# RefOsc10MHz_2V3.net
KiCad netlist of a schematic drawn in EAGLE
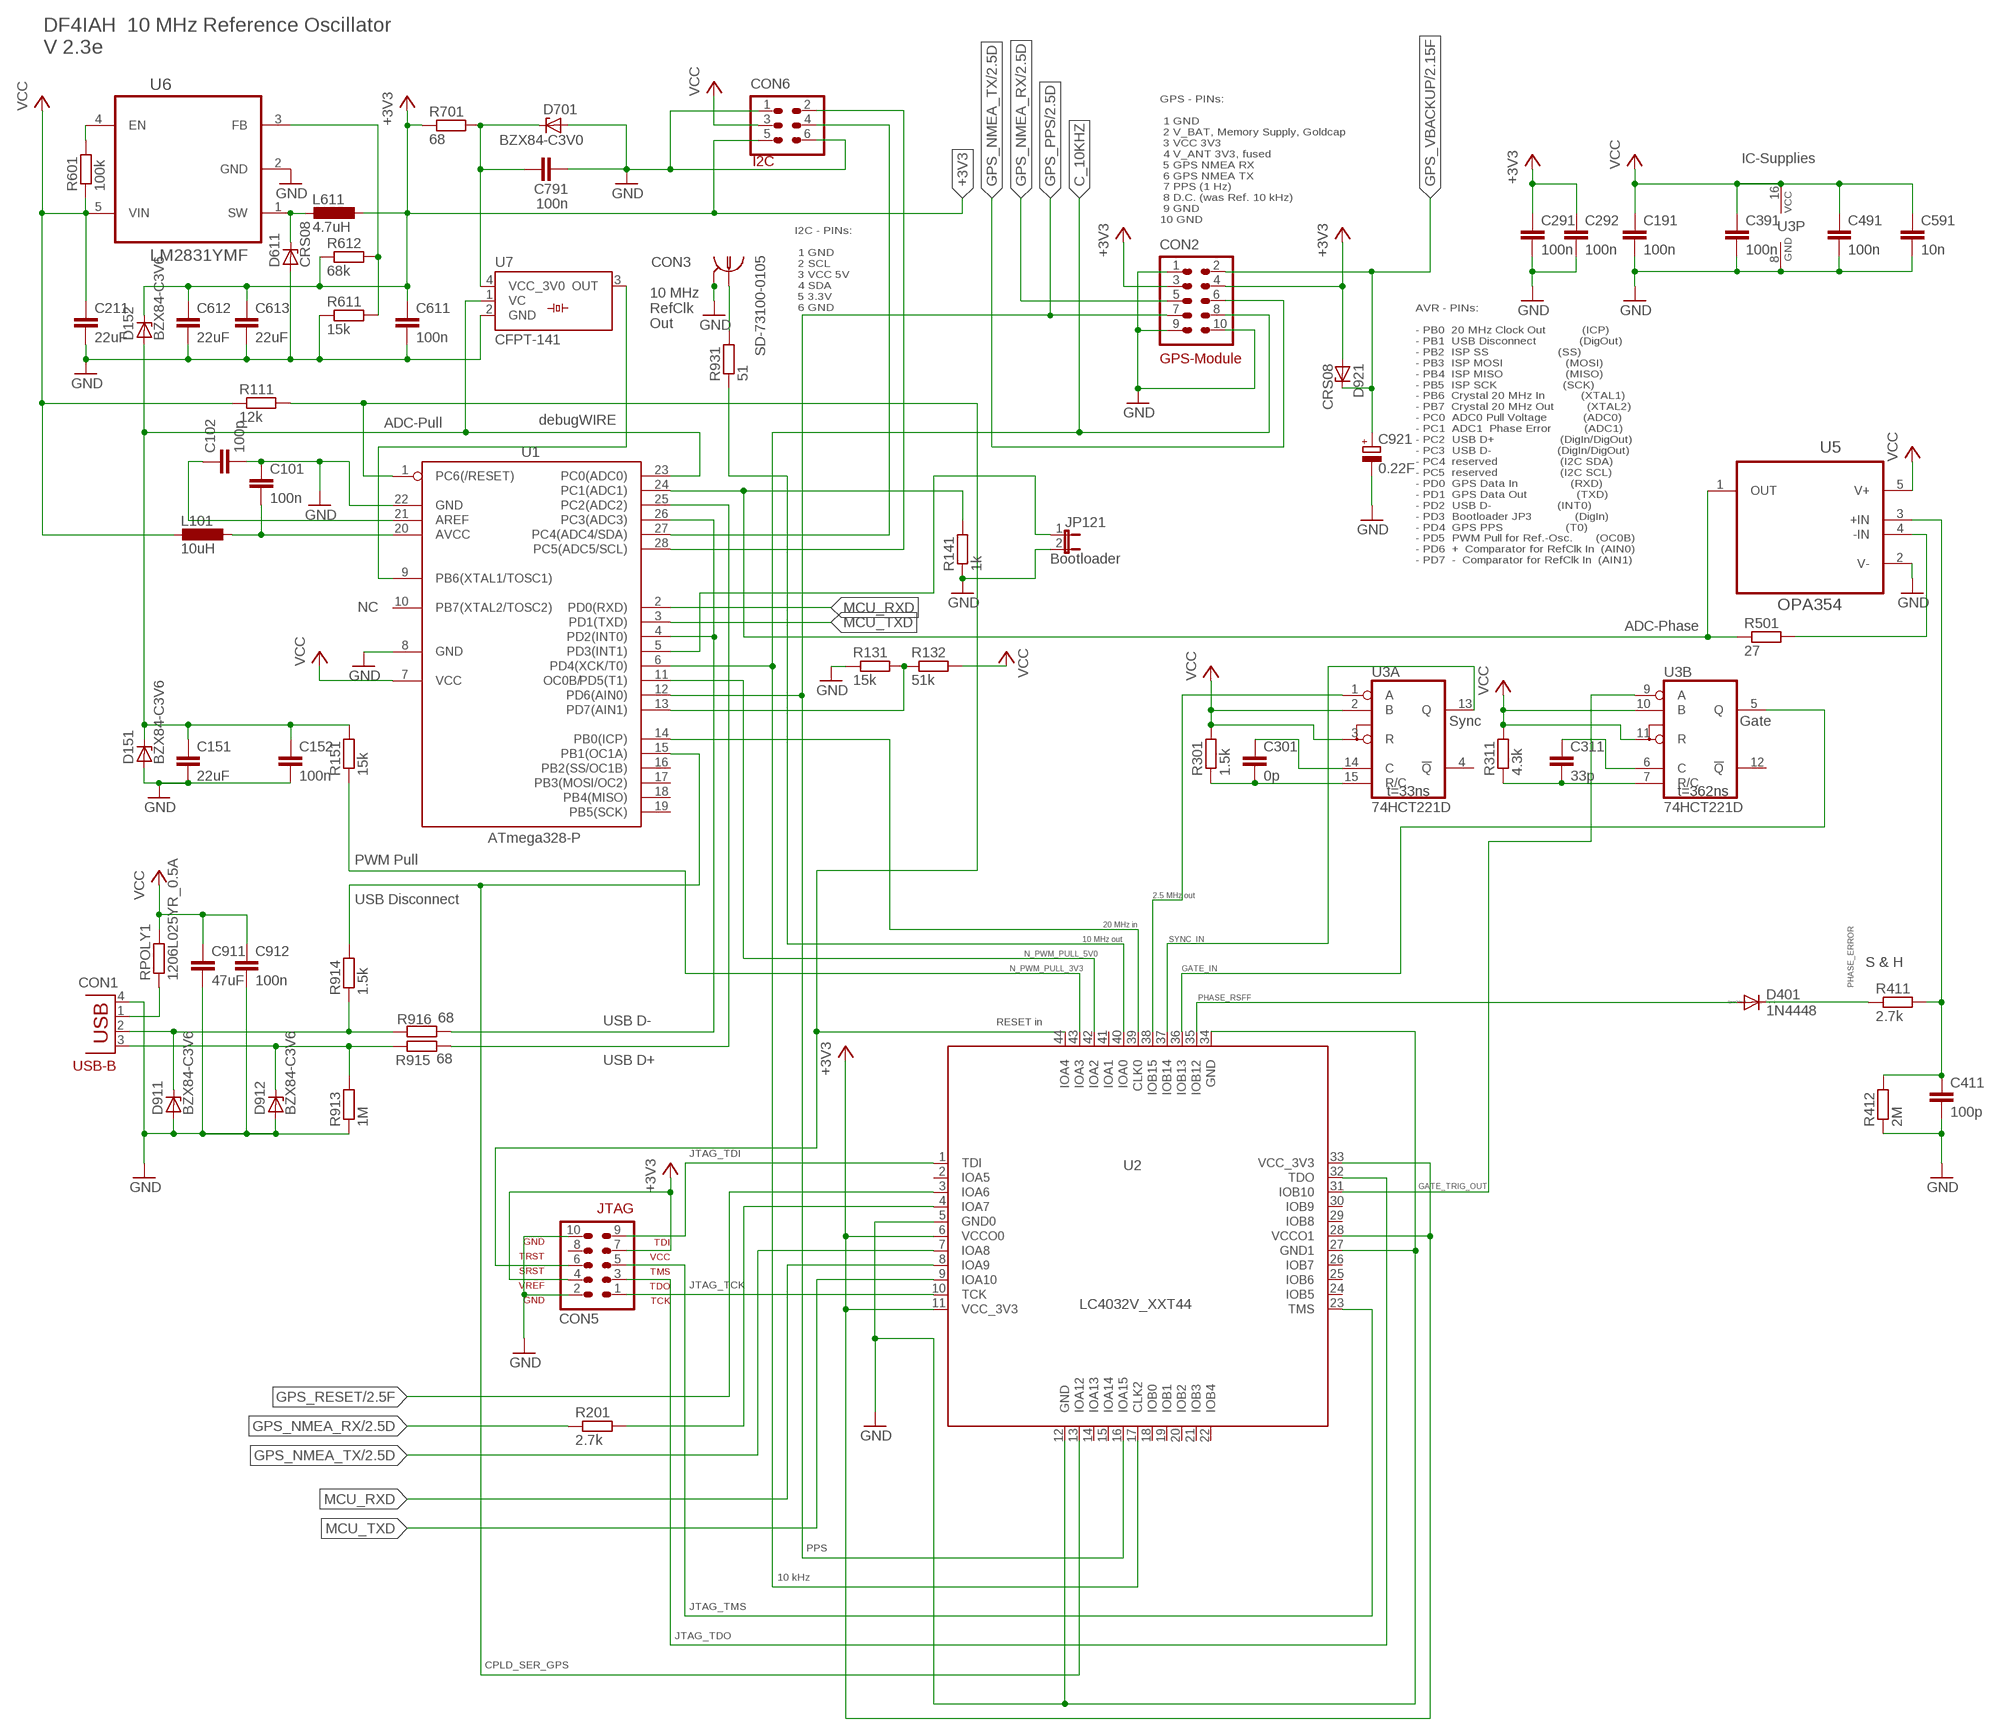
[diagram p0: schematic, sheet 1]
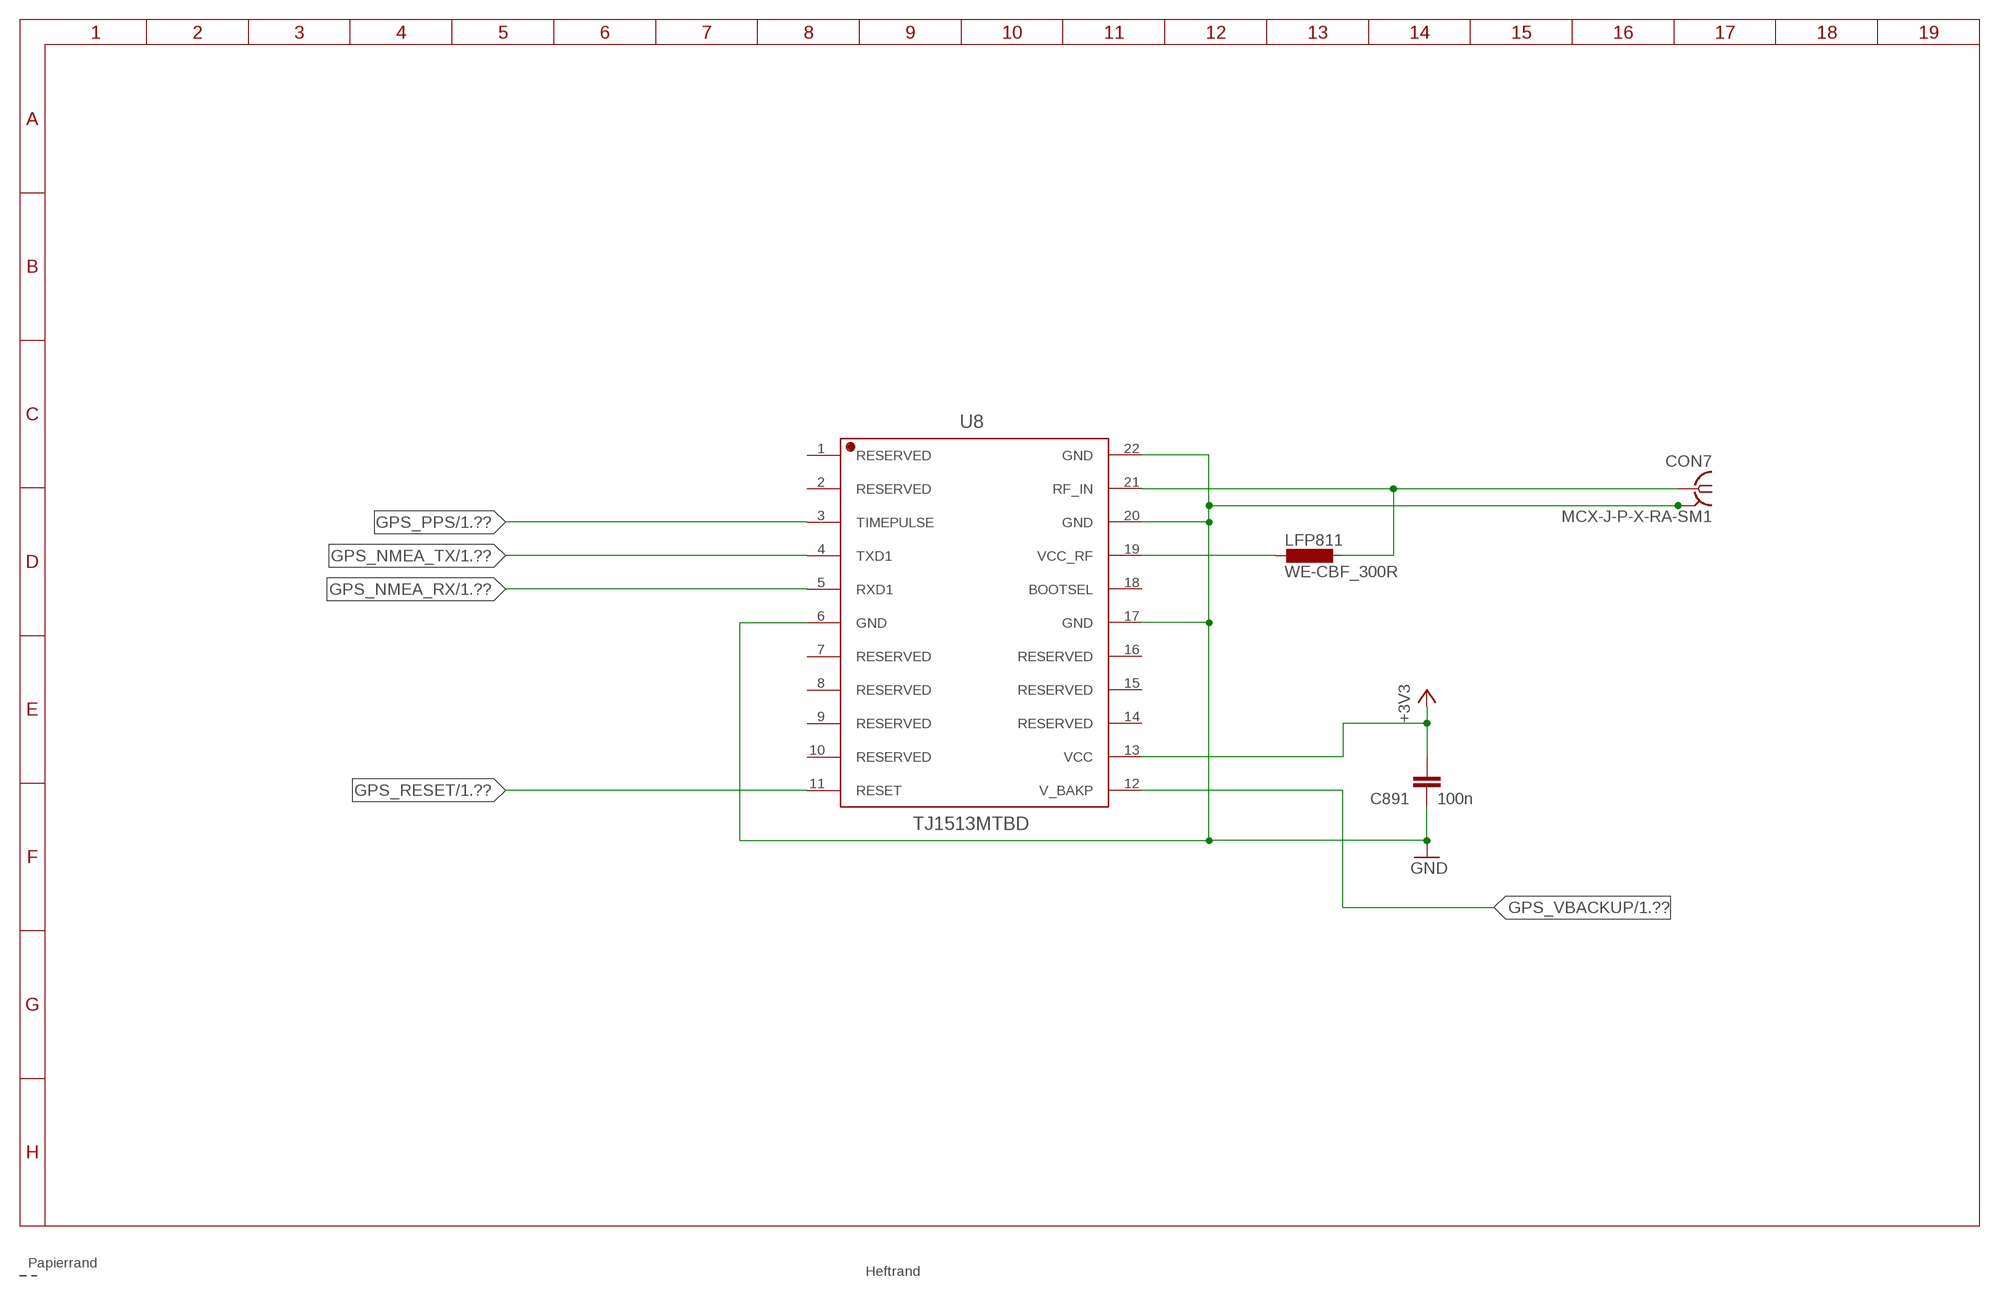
[diagram p1: schematic, sheet 2]
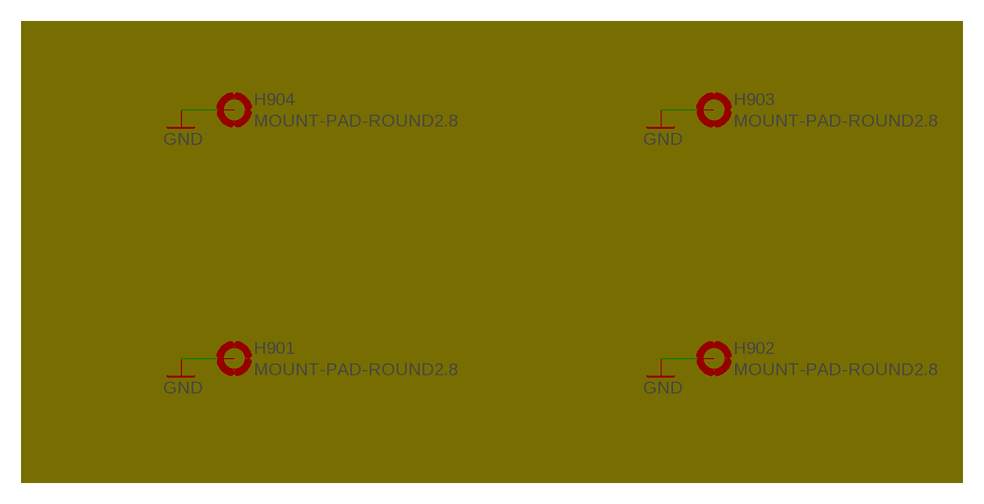
[diagram p2: schematic, sheet 3]

(export (version "E")
  (design (tool "Eeschema 10.0.6"))
  (components
    (comp (ref "C101")
      (value "100n")
      (footprint "eagle-import:C0805")
      (libsource (lib "eagle-import") (part "rcl_C-EUC0805"))
    )
    (comp (ref "C102")
      (value "100p")
      (footprint "eagle-import:C0805")
      (libsource (lib "eagle-import") (part "rcl_C-EUC0805"))
    )
    (comp (ref "C151")
      (value "22uF")
      (footprint "eagle-import:C0805")
      (libsource (lib "eagle-import") (part "rcl_C-EUC0805"))
    )
    (comp (ref "C152")
      (value "100n")
      (footprint "eagle-import:C0805")
      (libsource (lib "eagle-import") (part "rcl_C-EUC0805"))
    )
    (comp (ref "C191")
      (value "100n")
      (footprint "eagle-import:C0805")
      (libsource (lib "eagle-import") (part "rcl_C-EUC0805"))
    )
    (comp (ref "C211")
      (value "22uF")
      (footprint "eagle-import:C0805")
      (libsource (lib "eagle-import") (part "rcl_C-EUC0805"))
    )
    (comp (ref "C291")
      (value "100n")
      (footprint "eagle-import:C0805")
      (libsource (lib "eagle-import") (part "rcl_C-EUC0805"))
    )
    (comp (ref "C292")
      (value "100n")
      (footprint "eagle-import:C0805")
      (libsource (lib "eagle-import") (part "rcl_C-EUC0805"))
    )
    (comp (ref "C301")
      (value "0p")
      (footprint "eagle-import:C0805")
      (libsource (lib "eagle-import") (part "rcl_C-EUC0805"))
    )
    (comp (ref "C311")
      (value "33p")
      (footprint "eagle-import:C0805")
      (libsource (lib "eagle-import") (part "rcl_C-EUC0805"))
    )
    (comp (ref "C391")
      (value "100n")
      (footprint "eagle-import:C0805")
      (libsource (lib "eagle-import") (part "rcl_C-EUC0805"))
    )
    (comp (ref "C411")
      (value "100p")
      (footprint "eagle-import:C0805")
      (libsource (lib "eagle-import") (part "rcl_C-EUC0805"))
    )
    (comp (ref "C491")
      (value "100n")
      (footprint "eagle-import:C0805")
      (libsource (lib "eagle-import") (part "rcl_C-EUC0805"))
    )
    (comp (ref "C591")
      (value "10n")
      (footprint "eagle-import:C0805")
      (libsource (lib "eagle-import") (part "rcl_C-EUC0805"))
    )
    (comp (ref "C611")
      (value "100n")
      (footprint "eagle-import:C0805")
      (libsource (lib "eagle-import") (part "rcl_C-EUC0805"))
    )
    (comp (ref "C612")
      (value "22uF")
      (footprint "eagle-import:C0805")
      (libsource (lib "eagle-import") (part "rcl_C-EUC0805"))
    )
    (comp (ref "C613")
      (value "22uF")
      (footprint "eagle-import:C0805")
      (libsource (lib "eagle-import") (part "rcl_C-EUC0805"))
    )
    (comp (ref "C791")
      (value "100n")
      (footprint "eagle-import:C0805")
      (libsource (lib "eagle-import") (part "rcl_C-EUC0805"))
    )
    (comp (ref "C911")
      (value "47uF")
      (footprint "eagle-import:C0805")
      (libsource (lib "eagle-import") (part "rcl_C-EUC0805"))
    )
    (comp (ref "C912")
      (value "100n")
      (footprint "eagle-import:C0805")
      (libsource (lib "eagle-import") (part "rcl_C-EUC0805"))
    )
    (comp (ref "C921")
      (value "0.22F")
      (footprint "eagle-import:140CLH-1010")
      (libsource (lib "eagle-import") (part "CPOL-EU140CLH-1010"))
    )
    (comp (ref "CON1")
      (value "TYCO-AMP_USBUSB-B_SMT")
      (footprint "eagle-import:TYCO-AMP_USB-B_SMT")
      (fields (field (name "MF") "TYCO-AMP") (field (name "MPN") "1734346"))
      (libsource (lib "eagle-import") (part "TYCO-AMP_USBUSB-B_SMT"))
    )
    (comp (ref "CON2")
      (value "HEADER-2X5")
      (footprint "eagle-import:2X05")
      (libsource (lib "eagle-import") (part "HEADER-2X5"))
    )
    (comp (ref "CON3")
      (value "SD-73100-0105")
      (footprint "eagle-import:MOLEX_BNC-JACK-50R_SD-73100-0105")
      (fields (field (name "MF") "MOLEX"))
      (libsource (lib "eagle-import") (part "MOLEX_BNC-JACK-50R_SD-73100-0105"))
    )
    (comp (ref "CON5")
      (value "AVR-JTAG-10")
      (footprint "eagle-import:AVR-JTAG-10")
      (libsource (lib "eagle-import") (part "AVR-JTAG-10"))
    )
    (comp (ref "CON6")
      (value "HEADER-2X3")
      (footprint "eagle-import:2X03")
      (libsource (lib "eagle-import") (part "HEADER-2X3"))
    )
    (comp (ref "D151")
      (value "BZX84-C3V6")
      (footprint "eagle-import:TO236")
      (libsource (lib "eagle-import") (part "BZX84CSMD"))
    )
    (comp (ref "D152")
      (value "BZX84-C3V6")
      (footprint "eagle-import:TO236")
      (libsource (lib "eagle-import") (part "BZX84CSMD"))
    )
    (comp (ref "D401")
      (value "1N4448")
      (footprint "eagle-import:DO35-7")
      (libsource (lib "eagle-import") (part "1N4148DO35-7"))
    )
    (comp (ref "D611")
      (value "CRS08")
      (footprint "eagle-import:SOD80C")
      (libsource (lib "eagle-import") (part "ZENER-DIODESOD80C"))
    )
    (comp (ref "D701")
      (value "BZX84-C3V0")
      (footprint "eagle-import:TO236")
      (libsource (lib "eagle-import") (part "BZX84CSMD"))
    )
    (comp (ref "D911")
      (value "BZX84-C3V6")
      (footprint "eagle-import:TO236")
      (libsource (lib "eagle-import") (part "BZX84CSMD"))
    )
    (comp (ref "D912")
      (value "BZX84-C3V6")
      (footprint "eagle-import:TO236")
      (libsource (lib "eagle-import") (part "BZX84CSMD"))
    )
    (comp (ref "D921")
      (value "CRS08")
      (footprint "eagle-import:SOD80C")
      (libsource (lib "eagle-import") (part "ZENER-DIODESOD80C"))
    )
    (comp (ref "JP121")
      (value "JP1E")
      (footprint "eagle-import:JP1")
      (libsource (lib "eagle-import") (part "JP1E"))
    )
    (comp (ref "L101")
      (value "10uH")
      (footprint "eagle-import:L1812")
      (libsource (lib "eagle-import") (part "rcl_L-EUL1812"))
    )
    (comp (ref "L611")
      (value "4.7uH")
      (footprint "eagle-import:L5650M")
      (libsource (lib "eagle-import") (part "rcl_L-EUL5650M"))
    )
    (comp (ref "R111")
      (value "12k")
      (footprint "eagle-import:R0805")
      (libsource (lib "eagle-import") (part "R-EU_R0805"))
    )
    (comp (ref "R131")
      (value "15k")
      (footprint "eagle-import:R0805")
      (libsource (lib "eagle-import") (part "R-EU_R0805"))
    )
    (comp (ref "R132")
      (value "51k")
      (footprint "eagle-import:R0805")
      (libsource (lib "eagle-import") (part "R-EU_R0805"))
    )
    (comp (ref "R141")
      (value "1k")
      (footprint "eagle-import:R0805")
      (libsource (lib "eagle-import") (part "R-EU_R0805"))
    )
    (comp (ref "R151")
      (value "15k")
      (footprint "eagle-import:R0805")
      (libsource (lib "eagle-import") (part "R-EU_R0805"))
    )
    (comp (ref "R201")
      (value "2.7k")
      (footprint "eagle-import:R0805")
      (libsource (lib "eagle-import") (part "R-EU_R0805"))
    )
    (comp (ref "R301")
      (value "1.5k")
      (footprint "eagle-import:R0805")
      (libsource (lib "eagle-import") (part "R-EU_R0805"))
    )
    (comp (ref "R311")
      (value "4.3k")
      (footprint "eagle-import:R0805")
      (libsource (lib "eagle-import") (part "R-EU_R0805"))
    )
    (comp (ref "R411")
      (value "2.7k")
      (footprint "eagle-import:R0805")
      (libsource (lib "eagle-import") (part "R-EU_R0805"))
    )
    (comp (ref "R412")
      (value "2M")
      (footprint "eagle-import:R0805")
      (libsource (lib "eagle-import") (part "R-EU_R0805"))
    )
    (comp (ref "R501")
      (value "27")
      (footprint "eagle-import:R0805")
      (libsource (lib "eagle-import") (part "R-EU_R0805"))
    )
    (comp (ref "R601")
      (value "100k")
      (footprint "eagle-import:R0805")
      (libsource (lib "eagle-import") (part "R-EU_R0805"))
    )
    (comp (ref "R611")
      (value "15k")
      (footprint "eagle-import:R0805")
      (libsource (lib "eagle-import") (part "R-EU_R0805"))
    )
    (comp (ref "R612")
      (value "68k")
      (footprint "eagle-import:R0805")
      (libsource (lib "eagle-import") (part "R-EU_R0805"))
    )
    (comp (ref "R701")
      (value "68")
      (footprint "eagle-import:R0805")
      (libsource (lib "eagle-import") (part "R-EU_R0805"))
    )
    (comp (ref "R913")
      (value "1M")
      (footprint "eagle-import:R0805")
      (libsource (lib "eagle-import") (part "R-EU_R0805"))
    )
    (comp (ref "R914")
      (value "1.5k")
      (footprint "eagle-import:R0805")
      (libsource (lib "eagle-import") (part "R-EU_R0805"))
    )
    (comp (ref "R915")
      (value "68")
      (footprint "eagle-import:R0805")
      (libsource (lib "eagle-import") (part "R-EU_R0805"))
    )
    (comp (ref "R916")
      (value "68")
      (footprint "eagle-import:R0805")
      (libsource (lib "eagle-import") (part "R-EU_R0805"))
    )
    (comp (ref "R931")
      (value "51")
      (footprint "eagle-import:R0805")
      (libsource (lib "eagle-import") (part "R-EU_R0805"))
    )
    (comp (ref "RPOLY1")
      (value "1206L025YR_0.5A")
      (footprint "eagle-import:M1206")
      (libsource (lib "eagle-import") (part "R-EU_M1206"))
    )
    (comp (ref "U1")
      (value "ATmega328-P")
      (footprint "eagle-import:DIL28-3")
      (libsource (lib "eagle-import") (part "MEGA8-P"))
    )
    (comp (ref "U2")
      (value "LC4032V_XXT44")
      (footprint "eagle-import:TQFP44")
      (libsource (lib "eagle-import") (part "LC4032V_XXT44"))
    )
    (comp (ref "U3")
      (value "74HCT221D")
      (footprint "eagle-import:SO16")
      (libsource (lib "eagle-import") (part "74221DHCT"))
    )
    (comp (ref "U5")
      (value "OPA354")
      (footprint "eagle-import:SOT-23-5")
      (fields (field (name "MPN") "OPA354AIDBVT"))
      (libsource (lib "eagle-import") (part "OPA354"))
    )
    (comp (ref "U6")
      (value "LM2831YMF")
      (footprint "eagle-import:SOT95P280X145-5N")
      (fields (field (name "MPN") "LM2831YMF/NOPB"))
      (libsource (lib "eagle-import") (part "LM2831YMF"))
    )
    (comp (ref "U7")
      (value "CFPT-141")
      (footprint "eagle-import:CFPT-141")
      (fields (field (name "MF") "IQD-FREQUENCY-PRODUCTS") (field (name "MPN") "LFTVXO022175"))
      (libsource (lib "eagle-import") (part "CFPT-141"))
    )
    (comp (ref "H901")
      (value "MOUNT-PAD-ROUND2.8")
      (footprint "eagle-import:2,8-PAD")
      (libsource (lib "eagle-import") (part "MOUNT-PAD-ROUND2.8"))
    )
    (comp (ref "H902")
      (value "MOUNT-PAD-ROUND2.8")
      (footprint "eagle-import:2,8-PAD")
      (libsource (lib "eagle-import") (part "MOUNT-PAD-ROUND2.8"))
    )
    (comp (ref "H903")
      (value "MOUNT-PAD-ROUND2.8")
      (footprint "eagle-import:2,8-PAD")
      (libsource (lib "eagle-import") (part "MOUNT-PAD-ROUND2.8"))
    )
    (comp (ref "H904")
      (value "MOUNT-PAD-ROUND2.8")
      (footprint "eagle-import:2,8-PAD")
      (libsource (lib "eagle-import") (part "MOUNT-PAD-ROUND2.8"))
    )
    (comp (ref "C891")
      (value "100n")
      (footprint "eagle-import:C0805")
      (libsource (lib "eagle-import") (part "C-EUC0805"))
    )
    (comp (ref "CON7")
      (value "MCX-J-P-X-RA-SM1")
      (footprint "eagle-import:MCX-J-P-X-RA-SM1")
      (libsource (lib "eagle-import") (part "MCX-J-P-X-RA-SM1"))
    )
    (comp (ref "LFP811")
      (value "WE-CBF_300R")
      (footprint "eagle-import:L3216C")
      (libsource (lib "eagle-import") (part "L-EUL3216C"))
    )
    (comp (ref "U8")
      (value "TJ1513MTBD")
      (footprint "eagle-import:TJ1513MTBD")
      (libsource (lib "eagle-import") (part "TJ1513MTBD"))
    )
  )
  (nets
    (net (code "1") (name "+3V3") (class "Default")
      (node (ref "C291") (pin "1") (pinfunction "1_1") (pintype "passive"))
      (node (ref "C292") (pin "1") (pinfunction "1_1") (pintype "passive"))
      (node (ref "C611") (pin "1") (pinfunction "1_1") (pintype "passive"))
      (node (ref "C612") (pin "1") (pinfunction "1_1") (pintype "passive"))
      (node (ref "C613") (pin "1") (pinfunction "1_1") (pintype "passive"))
      (node (ref "C891") (pin "1") (pinfunction "1_1") (pintype "passive"))
      (node (ref "CON2") (pin "3") (pinfunction "3_3") (pintype "passive"))
      (node (ref "CON2") (pin "4") (pinfunction "4_4") (pintype "passive"))
      (node (ref "CON5") (pin "4") (pinfunction "4_4") (pintype "passive"))
      (node (ref "CON5") (pin "7") (pinfunction "7_7") (pintype "passive"))
      (node (ref "CON6") (pin "5") (pinfunction "5_5") (pintype "passive"))
      (node (ref "D152") (pin "C") (pinfunction "C_C") (pintype "passive"))
      (node (ref "D921") (pin "A") (pinfunction "A_A") (pintype "passive"))
      (node (ref "L611") (pin "1") (pinfunction "1_1") (pintype "passive"))
      (node (ref "R612") (pin "1") (pinfunction "1_1") (pintype "passive"))
      (node (ref "R701") (pin "1") (pinfunction "1_1") (pintype "passive"))
      (node (ref "U2") (pin "11") (pinfunction "VCC_3V3_11") (pintype "power_in"))
      (node (ref "U2") (pin "28") (pinfunction "VCCO1_28") (pintype "power_in"))
      (node (ref "U2") (pin "33") (pinfunction "VCC_3V3_33") (pintype "power_in"))
      (node (ref "U2") (pin "6") (pinfunction "VCCO0_6") (pintype "power_in"))
      (node (ref "U8") (pin "13") (pinfunction "VCC_13") (pintype "power_in"))
    )
    (net (code "2") (name "C_10KHZ") (class "Default")
      (node (ref "CON2") (pin "8") (pinfunction "8_8") (pintype "passive"))
      (node (ref "U1") (pin "6") (pinfunction "PD4(XCK/T0)_6") (pintype "bidirectional"))
      (node (ref "U2") (pin "17") (pinfunction "CLK2_17") (pintype "input"))
    )
    (net (code "3") (name "GATE_IN") (class "Default")
      (node (ref "U2") (pin "36") (pinfunction "IOB13_36") (pintype "bidirectional"))
      (node (ref "U3") (pin "5") (pinfunction "Q_5") (pintype "output"))
    )
    (net (code "4") (name "GATE_TRIG_OUT") (class "Default")
      (node (ref "U2") (pin "31") (pinfunction "IOB10_31") (pintype "bidirectional"))
      (node (ref "U3") (pin "9") (pinfunction "A_9") (pintype "input"))
    )
    (net (code "5") (name "GND") (class "Default")
      (node (ref "C101") (pin "1") (pinfunction "1_1") (pintype "passive"))
      (node (ref "C102") (pin "2") (pinfunction "2_2") (pintype "passive"))
      (node (ref "C151") (pin "2") (pinfunction "2_2") (pintype "passive"))
      (node (ref "C152") (pin "2") (pinfunction "2_2") (pintype "passive"))
      (node (ref "C191") (pin "2") (pinfunction "2_2") (pintype "passive"))
      (node (ref "C211") (pin "2") (pinfunction "2_2") (pintype "passive"))
      (node (ref "C291") (pin "2") (pinfunction "2_2") (pintype "passive"))
      (node (ref "C292") (pin "2") (pinfunction "2_2") (pintype "passive"))
      (node (ref "C391") (pin "2") (pinfunction "2_2") (pintype "passive"))
      (node (ref "C411") (pin "2") (pinfunction "2_2") (pintype "passive"))
      (node (ref "C491") (pin "2") (pinfunction "2_2") (pintype "passive"))
      (node (ref "C591") (pin "2") (pinfunction "2_2") (pintype "passive"))
      (node (ref "C611") (pin "2") (pinfunction "2_2") (pintype "passive"))
      (node (ref "C612") (pin "2") (pinfunction "2_2") (pintype "passive"))
      (node (ref "C613") (pin "2") (pinfunction "2_2") (pintype "passive"))
      (node (ref "C791") (pin "2") (pinfunction "2_2") (pintype "passive"))
      (node (ref "C891") (pin "2") (pinfunction "2_2") (pintype "passive"))
      (node (ref "C911") (pin "2") (pinfunction "2_2") (pintype "passive"))
      (node (ref "C912") (pin "2") (pinfunction "2_2") (pintype "passive"))
      (node (ref "C921") (pin "-") (pinfunction "-_-") (pintype "passive"))
      (node (ref "CON1") (pin "4") (pinfunction "GND_4") (pintype "bidirectional"))
      (node (ref "CON2") (pin "1") (pinfunction "1_1") (pintype "passive"))
      (node (ref "CON2") (pin "10") (pinfunction "10_10") (pintype "passive"))
      (node (ref "CON2") (pin "9") (pinfunction "9_9") (pintype "passive"))
      (node (ref "CON3") (pin "2") (pinfunction "2_2") (pintype "passive"))
      (node (ref "CON3") (pin "3") (pinfunction "3_3") (pintype "passive"))
      (node (ref "CON5") (pin "10") (pinfunction "10_10") (pintype "passive"))
      (node (ref "CON5") (pin "2") (pinfunction "2_2") (pintype "passive"))
      (node (ref "CON6") (pin "1") (pinfunction "1_1") (pintype "passive"))
      (node (ref "CON6") (pin "6") (pinfunction "6_6") (pintype "passive"))
      (node (ref "CON7") (pin "2") (pinfunction "2_2") (pintype "passive"))
      (node (ref "CON7") (pin "3") (pinfunction "3_3") (pintype "passive"))
      (node (ref "CON7") (pin "4") (pinfunction "4_4") (pintype "passive"))
      (node (ref "CON7") (pin "5") (pinfunction "5_5") (pintype "passive"))
      (node (ref "D151") (pin "A") (pinfunction "A_A") (pintype "passive"))
      (node (ref "D611") (pin "A") (pinfunction "A_A") (pintype "passive"))
      (node (ref "D701") (pin "A") (pinfunction "A_A") (pintype "passive"))
      (node (ref "D911") (pin "A") (pinfunction "A_A") (pintype "passive"))
      (node (ref "D912") (pin "A") (pinfunction "A_A") (pintype "passive"))
      (node (ref "H901") (pin "B2,8") (pinfunction "MOUNT_B2,8") (pintype "passive"))
      (node (ref "H902") (pin "B2,8") (pinfunction "MOUNT_B2,8") (pintype "passive"))
      (node (ref "H903") (pin "B2,8") (pinfunction "MOUNT_B2,8") (pintype "passive"))
      (node (ref "H904") (pin "B2,8") (pinfunction "MOUNT_B2,8") (pintype "passive"))
      (node (ref "JP121") (pin "2") (pinfunction "2_2") (pintype "passive"))
      (node (ref "R131") (pin "1") (pinfunction "1_1") (pintype "passive"))
      (node (ref "R141") (pin "1") (pinfunction "1_1") (pintype "passive"))
      (node (ref "R412") (pin "1") (pinfunction "1_1") (pintype "passive"))
      (node (ref "R611") (pin "1") (pinfunction "1_1") (pintype "passive"))
      (node (ref "R913") (pin "1") (pinfunction "1_1") (pintype "passive"))
      (node (ref "U1") (pin "22") (pinfunction "GND_22") (pintype "power_in"))
      (node (ref "U1") (pin "8") (pinfunction "GND_8") (pintype "power_in"))
      (node (ref "U2") (pin "12") (pinfunction "GND_12") (pintype "power_in"))
      (node (ref "U2") (pin "27") (pinfunction "GND1_27") (pintype "power_in"))
      (node (ref "U2") (pin "34") (pinfunction "GND_34") (pintype "power_in"))
      (node (ref "U2") (pin "5") (pinfunction "GND0_5") (pintype "power_in"))
      (node (ref "U3") (pin "8") (pinfunction "GND_8") (pintype "power_in"))
      (node (ref "U5") (pin "2") (pinfunction "V-_2") (pintype "power_in"))
      (node (ref "U6") (pin "2") (pinfunction "GND_2") (pintype "passive"))
      (node (ref "U7") (pin "2") (pinfunction "GND_2") (pintype "power_in"))
      (node (ref "U8") (pin "17") (pinfunction "GND_17") (pintype "power_in"))
      (node (ref "U8") (pin "20") (pinfunction "GND_20") (pintype "power_in"))
      (node (ref "U8") (pin "22") (pinfunction "GND_22") (pintype "power_in"))
      (node (ref "U8") (pin "6") (pinfunction "GND_6") (pintype "power_in"))
    )
    (net (code "6") (name "GPS_NMEA_RX") (class "Default")
      (node (ref "CON2") (pin "5") (pinfunction "5_5") (pintype "passive"))
      (node (ref "R201") (pin "1") (pinfunction "1_1") (pintype "passive"))
      (node (ref "U8") (pin "5") (pinfunction "RXD1_5") (pintype "input"))
    )
    (net (code "7") (name "GPS_NMEA_TX") (class "Default")
      (node (ref "CON2") (pin "6") (pinfunction "6_6") (pintype "passive"))
      (node (ref "U2") (pin "7") (pinfunction "IOA8_7") (pintype "bidirectional"))
      (node (ref "U8") (pin "4") (pinfunction "TXD1_4") (pintype "output"))
    )
    (net (code "8") (name "GPS_PPS") (class "Default")
      (node (ref "CON2") (pin "7") (pinfunction "7_7") (pintype "passive"))
      (node (ref "U1") (pin "12") (pinfunction "PD6(AIN0)_12") (pintype "bidirectional"))
      (node (ref "U2") (pin "16") (pinfunction "IOA15_16") (pintype "bidirectional"))
      (node (ref "U8") (pin "3") (pinfunction "TIMEPULSE_3") (pintype "output"))
    )
    (net (code "9") (name "GPS_RESET") (class "Default")
      (node (ref "U2") (pin "3") (pinfunction "IOA6_3") (pintype "bidirectional"))
      (node (ref "U8") (pin "11") (pinfunction "RESET_11") (pintype "passive"))
    )
    (net (code "10") (name "GPS_VBACKUP") (class "Default")
      (node (ref "C921") (pin "+") (pinfunction "+_+") (pintype "passive"))
      (node (ref "CON2") (pin "2") (pinfunction "2_2") (pintype "passive"))
      (node (ref "D921") (pin "C") (pinfunction "C_C") (pintype "passive"))
      (node (ref "U8") (pin "12") (pinfunction "V_BAKP_12") (pintype "power_in"))
    )
    (net (code "11") (name "MCU_RXD") (class "Default")
      (node (ref "U1") (pin "2") (pinfunction "PD0(RXD)_2") (pintype "bidirectional"))
      (node (ref "U2") (pin "8") (pinfunction "IOA9_8") (pintype "bidirectional"))
    )
    (net (code "12") (name "MCU_TXD") (class "Default")
      (node (ref "U1") (pin "3") (pinfunction "PD1(TXD)_3") (pintype "bidirectional"))
      (node (ref "U2") (pin "9") (pinfunction "IOA10_9") (pintype "bidirectional"))
    )
    (net (code "13") (name "N_PWM_PULL_3V3") (class "Default")
      (node (ref "R151") (pin "1") (pinfunction "1_1") (pintype "passive"))
      (node (ref "U2") (pin "43") (pinfunction "IOA3_43") (pintype "bidirectional"))
    )
    (net (code "14") (name "N_PWM_PULL_5V0") (class "Default")
      (node (ref "U1") (pin "11") (pinfunction "PD5(T1)_11") (pintype "bidirectional"))
      (node (ref "U2") (pin "42") (pinfunction "IOA2_42") (pintype "bidirectional"))
    )
    (net (code "15") (name "Net-(CON1-D+)") (class "Default")
      (node (ref "CON1") (pin "3") (pinfunction "D+_3") (pintype "bidirectional"))
      (node (ref "D912") (pin "C") (pinfunction "C_C") (pintype "passive"))
      (node (ref "R913") (pin "2") (pinfunction "2_2") (pintype "passive"))
      (node (ref "R915") (pin "1") (pinfunction "1_1") (pintype "passive"))
    )
    (net (code "16") (name "Net-(CON1-D-)") (class "Default")
      (node (ref "CON1") (pin "2") (pinfunction "D-_2") (pintype "bidirectional"))
      (node (ref "D911") (pin "C") (pinfunction "C_C") (pintype "passive"))
      (node (ref "R914") (pin "1") (pinfunction "1_1") (pintype "passive"))
      (node (ref "R916") (pin "1") (pinfunction "1_1") (pintype "passive"))
    )
    (net (code "17") (name "Net-(CON1-VBUS)") (class "Default")
      (node (ref "CON1") (pin "1") (pinfunction "VBUS_1") (pintype "bidirectional"))
      (node (ref "RPOLY1") (pin "1") (pinfunction "1_1") (pintype "passive"))
    )
    (net (code "18") (name "Net-(CON3-Pad1)") (class "Default")
      (node (ref "CON3") (pin "1") (pinfunction "1_1") (pintype "passive"))
      (node (ref "R931") (pin "2") (pinfunction "2_2") (pintype "passive"))
    )
    (net (code "19") (name "Net-(U1-AREF)") (class "Default")
      (node (ref "C102") (pin "1") (pinfunction "1_1") (pintype "passive"))
      (node (ref "U1") (pin "21") (pinfunction "AREF_21") (pintype "passive"))
    )
    (net (code "20") (name "Net-(U1-AVCC)") (class "Default")
      (node (ref "C101") (pin "2") (pinfunction "2_2") (pintype "passive"))
      (node (ref "L101") (pin "1") (pinfunction "1_1") (pintype "passive"))
      (node (ref "U1") (pin "20") (pinfunction "AVCC_20") (pintype "power_in"))
    )
    (net (code "21") (name "Net-(U1-PB0(ICP))") (class "Default")
      (node (ref "U1") (pin "14") (pinfunction "PB0(ICP)_14") (pintype "bidirectional"))
      (node (ref "U2") (pin "39") (pinfunction "CLK0_39") (pintype "input"))
    )
    (net (code "22") (name "Net-(U1-PB1(OC1A))") (class "Default")
      (node (ref "R914") (pin "2") (pinfunction "2_2") (pintype "passive"))
      (node (ref "U1") (pin "15") (pinfunction "PB1(OC1A)_15") (pintype "bidirectional"))
      (node (ref "U2") (pin "13") (pinfunction "IOA12_13") (pintype "bidirectional"))
    )
    (net (code "23") (name "Net-(U1-PB6(XTAL1{slash}TOSC1))") (class "Default")
      (node (ref "U1") (pin "9") (pinfunction "PB6(XTAL1/TOSC1)_9") (pintype "bidirectional"))
      (node (ref "U7") (pin "3") (pinfunction "OUT_3") (pintype "output"))
    )
    (net (code "24") (name "Net-(U1-PC0(ADC0))") (class "Default")
      (node (ref "C151") (pin "1") (pinfunction "1_1") (pintype "passive"))
      (node (ref "C152") (pin "1") (pinfunction "1_1") (pintype "passive"))
      (node (ref "D151") (pin "C") (pinfunction "C_C") (pintype "passive"))
      (node (ref "D152") (pin "A") (pinfunction "A_A") (pintype "passive"))
      (node (ref "R151") (pin "2") (pinfunction "2_2") (pintype "passive"))
      (node (ref "U1") (pin "23") (pinfunction "PC0(ADC0)_23") (pintype "bidirectional"))
      (node (ref "U7") (pin "1") (pinfunction "VC_1") (pintype "input"))
    )
    (net (code "25") (name "Net-(U1-PC1(ADC1))") (class "Default")
      (node (ref "R141") (pin "2") (pinfunction "2_2") (pintype "passive"))
      (node (ref "R501") (pin "1") (pinfunction "1_1") (pintype "passive"))
      (node (ref "U1") (pin "24") (pinfunction "PC1(ADC1)_24") (pintype "bidirectional"))
      (node (ref "U5") (pin "1") (pinfunction "OUT_1") (pintype "output"))
    )
    (net (code "26") (name "Net-(U1-PC2(ADC2))") (class "Default")
      (node (ref "R915") (pin "2") (pinfunction "2_2") (pintype "passive"))
      (node (ref "U1") (pin "25") (pinfunction "PC2(ADC2)_25") (pintype "bidirectional"))
    )
    (net (code "27") (name "Net-(U1-PC3(ADC3))") (class "Default")
      (node (ref "R916") (pin "2") (pinfunction "2_2") (pintype "passive"))
      (node (ref "U1") (pin "26") (pinfunction "PC3(ADC3)_26") (pintype "bidirectional"))
      (node (ref "U1") (pin "4") (pinfunction "PD2(INT0)_4") (pintype "bidirectional"))
    )
    (net (code "28") (name "Net-(U1-PC4(ADC4{slash}SDA))") (class "Default")
      (node (ref "CON6") (pin "4") (pinfunction "4_4") (pintype "passive"))
      (node (ref "U1") (pin "27") (pinfunction "PC4(ADC4/SDA)_27") (pintype "bidirectional"))
    )
    (net (code "29") (name "Net-(U1-PC5(ADC5{slash}SCL))") (class "Default")
      (node (ref "CON6") (pin "2") (pinfunction "2_2") (pintype "passive"))
      (node (ref "U1") (pin "28") (pinfunction "PC5(ADC5/SCL)_28") (pintype "bidirectional"))
    )
    (net (code "30") (name "Net-(U1-PC6({slash}RESET))") (class "Default")
      (node (ref "CON5") (pin "6") (pinfunction "6_6") (pintype "passive"))
      (node (ref "R111") (pin "2") (pinfunction "2_2") (pintype "passive"))
      (node (ref "U1") (pin "1") (pinfunction "PC6(/RESET)_1") (pintype "bidirectional"))
      (node (ref "U2") (pin "44") (pinfunction "IOA4_44") (pintype "bidirectional"))
    )
    (net (code "31") (name "Net-(U1-PD3(INT1))") (class "Default")
      (node (ref "JP121") (pin "1") (pinfunction "1_1") (pintype "passive"))
      (node (ref "U1") (pin "5") (pinfunction "PD3(INT1)_5") (pintype "bidirectional"))
    )
    (net (code "32") (name "Net-(U1-PD7(AIN1))") (class "Default")
      (node (ref "R131") (pin "2") (pinfunction "2_2") (pintype "passive"))
      (node (ref "R132") (pin "1") (pinfunction "1_1") (pintype "passive"))
      (node (ref "U1") (pin "13") (pinfunction "PD7(AIN1)_13") (pintype "bidirectional"))
    )
    (net (code "33") (name "Net-(U2-IOA0)") (class "Default")
      (node (ref "R931") (pin "1") (pinfunction "1_1") (pintype "passive"))
      (node (ref "U2") (pin "40") (pinfunction "IOA0_40") (pintype "bidirectional"))
    )
    (net (code "34") (name "Net-(U2-IOA7)") (class "Default")
      (node (ref "R201") (pin "2") (pinfunction "2_2") (pintype "passive"))
      (node (ref "U2") (pin "4") (pinfunction "IOA7_4") (pintype "bidirectional"))
    )
    (net (code "35") (name "Net-(U2-IOB15)") (class "Default")
      (node (ref "U2") (pin "38") (pinfunction "IOB15_38") (pintype "bidirectional"))
      (node (ref "U3") (pin "1") (pinfunction "A_1") (pintype "input"))
    )
    (net (code "36") (name "Net-(U2-TCK)") (class "Default")
      (node (ref "CON5") (pin "1") (pinfunction "1_1") (pintype "passive"))
      (node (ref "U2") (pin "10") (pinfunction "TCK_10") (pintype "input"))
    )
    (net (code "37") (name "Net-(U2-TDI)") (class "Default")
      (node (ref "CON5") (pin "9") (pinfunction "9_9") (pintype "passive"))
      (node (ref "U2") (pin "1") (pinfunction "TDI_1") (pintype "input"))
    )
    (net (code "38") (name "Net-(U2-TDO)") (class "Default")
      (node (ref "CON5") (pin "3") (pinfunction "3_3") (pintype "passive"))
      (node (ref "U2") (pin "32") (pinfunction "TDO_32") (pintype "output"))
    )
    (net (code "39") (name "Net-(U2-TMS)") (class "Default")
      (node (ref "CON5") (pin "5") (pinfunction "5_5") (pintype "passive"))
      (node (ref "U2") (pin "23") (pinfunction "TMS_23") (pintype "input"))
    )
    (net (code "40") (name "Net-(U3A-C)") (class "Default")
      (node (ref "C301") (pin "1") (pinfunction "1_1") (pintype "passive"))
      (node (ref "U3") (pin "14") (pinfunction "C_14") (pintype "input"))
    )
    (net (code "41") (name "Net-(U3A-R{slash}C)") (class "Default")
      (node (ref "C301") (pin "2") (pinfunction "2_2") (pintype "passive"))
      (node (ref "R301") (pin "1") (pinfunction "1_1") (pintype "passive"))
      (node (ref "U3") (pin "15") (pinfunction "R/C_15") (pintype "input"))
    )
    (net (code "42") (name "Net-(U3B-C)") (class "Default")
      (node (ref "C311") (pin "1") (pinfunction "1_1") (pintype "passive"))
      (node (ref "U3") (pin "6") (pinfunction "C_6") (pintype "input"))
    )
    (net (code "43") (name "Net-(U3B-R{slash}C)") (class "Default")
      (node (ref "C311") (pin "2") (pinfunction "2_2") (pintype "passive"))
      (node (ref "R311") (pin "1") (pinfunction "1_1") (pintype "passive"))
      (node (ref "U3") (pin "7") (pinfunction "R/C_7") (pintype "input"))
    )
    (net (code "44") (name "Net-(U5-+IN)") (class "Default")
      (node (ref "C411") (pin "1") (pinfunction "1_1") (pintype "passive"))
      (node (ref "R411") (pin "2") (pinfunction "2_2") (pintype "passive"))
      (node (ref "R412") (pin "2") (pinfunction "2_2") (pintype "passive"))
      (node (ref "U5") (pin "3") (pinfunction "+IN_3") (pintype "input"))
    )
    (net (code "45") (name "Net-(U5--IN)") (class "Default")
      (node (ref "R501") (pin "2") (pinfunction "2_2") (pintype "passive"))
      (node (ref "U5") (pin "4") (pinfunction "-IN_4") (pintype "input"))
    )
    (net (code "46") (name "Net-(U6-EN)") (class "Default")
      (node (ref "R601") (pin "2") (pinfunction "2_2") (pintype "passive"))
      (node (ref "U6") (pin "4") (pinfunction "EN_4") (pintype "input"))
    )
    (net (code "47") (name "Net-(U6-FB)") (class "Default")
      (node (ref "R611") (pin "2") (pinfunction "2_2") (pintype "passive"))
      (node (ref "R612") (pin "2") (pinfunction "2_2") (pintype "passive"))
      (node (ref "U6") (pin "3") (pinfunction "FB_3") (pintype "input"))
    )
    (net (code "48") (name "Net-(U6-SW)") (class "Default")
      (node (ref "D611") (pin "C") (pinfunction "C_C") (pintype "passive"))
      (node (ref "L611") (pin "2") (pinfunction "2_2") (pintype "passive"))
      (node (ref "U6") (pin "1") (pinfunction "SW_1") (pintype "output"))
    )
    (net (code "49") (name "Net-(U7-VCC_3V0)") (class "Default")
      (node (ref "C791") (pin "1") (pinfunction "1_1") (pintype "passive"))
      (node (ref "D701") (pin "C") (pinfunction "C_C") (pintype "passive"))
      (node (ref "R701") (pin "2") (pinfunction "2_2") (pintype "passive"))
      (node (ref "U7") (pin "4") (pinfunction "VCC_3V0_4") (pintype "power_in"))
    )
    (net (code "50") (name "Net-(U8-RF_IN)") (class "Default")
      (node (ref "CON7") (pin "1") (pinfunction "1_1") (pintype "passive"))
      (node (ref "LFP811") (pin "1") (pinfunction "1_1") (pintype "passive"))
      (node (ref "U8") (pin "21") (pinfunction "RF_IN_21") (pintype "input"))
    )
    (net (code "51") (name "Net-(U8-VCC_RF)") (class "Default")
      (node (ref "LFP811") (pin "2") (pinfunction "2_2") (pintype "passive"))
      (node (ref "U8") (pin "19") (pinfunction "VCC_RF_19") (pintype "output"))
    )
    (net (code "52") (name "PHASE_ERROR") (class "Default")
      (node (ref "D401") (pin "C") (pinfunction "C_C") (pintype "passive"))
      (node (ref "R411") (pin "1") (pinfunction "1_1") (pintype "passive"))
    )
    (net (code "53") (name "PHASE_RSFF") (class "Default")
      (node (ref "D401") (pin "A") (pinfunction "A_A") (pintype "passive"))
      (node (ref "U2") (pin "35") (pinfunction "IOB12_35") (pintype "bidirectional"))
    )
    (net (code "54") (name "SYNC_IN") (class "Default")
      (node (ref "U2") (pin "37") (pinfunction "IOB14_37") (pintype "bidirectional"))
      (node (ref "U3") (pin "13") (pinfunction "Q_13") (pintype "output"))
    )
    (net (code "55") (name "VCC") (class "Default")
      (node (ref "C191") (pin "1") (pinfunction "1_1") (pintype "passive"))
      (node (ref "C211") (pin "1") (pinfunction "1_1") (pintype "passive"))
      (node (ref "C391") (pin "1") (pinfunction "1_1") (pintype "passive"))
      (node (ref "C491") (pin "1") (pinfunction "1_1") (pintype "passive"))
      (node (ref "C591") (pin "1") (pinfunction "1_1") (pintype "passive"))
      (node (ref "C911") (pin "1") (pinfunction "1_1") (pintype "passive"))
      (node (ref "C912") (pin "1") (pinfunction "1_1") (pintype "passive"))
      (node (ref "CON6") (pin "3") (pinfunction "3_3") (pintype "passive"))
      (node (ref "L101") (pin "2") (pinfunction "2_2") (pintype "passive"))
      (node (ref "R111") (pin "1") (pinfunction "1_1") (pintype "passive"))
      (node (ref "R132") (pin "2") (pinfunction "2_2") (pintype "passive"))
      (node (ref "R301") (pin "2") (pinfunction "2_2") (pintype "passive"))
      (node (ref "R311") (pin "2") (pinfunction "2_2") (pintype "passive"))
      (node (ref "R601") (pin "1") (pinfunction "1_1") (pintype "passive"))
      (node (ref "RPOLY1") (pin "2") (pinfunction "2_2") (pintype "passive"))
      (node (ref "U1") (pin "7") (pinfunction "VCC_7") (pintype "power_in"))
      (node (ref "U3") (pin "10") (pinfunction "B_10") (pintype "input"))
      (node (ref "U3") (pin "11") (pinfunction "R_11") (pintype "input"))
      (node (ref "U3") (pin "16") (pinfunction "VCC_16") (pintype "power_in"))
      (node (ref "U3") (pin "2") (pinfunction "B_2") (pintype "input"))
      (node (ref "U3") (pin "3") (pinfunction "R_3") (pintype "input"))
      (node (ref "U5") (pin "5") (pinfunction "V+_5") (pintype "power_in"))
      (node (ref "U6") (pin "5") (pinfunction "VIN_5") (pintype "power_in"))
    )
    (net (code "56") (name "unconnected-(CON5-Pad8)") (class "Default")
      (node (ref "CON5") (pin "8") (pinfunction "8_8") (pintype "passive"))
    )
    (net (code "57") (name "unconnected-(U1-PB2(SS{slash}OC1B)-Pad16)") (class "Default")
      (node (ref "U1") (pin "16") (pinfunction "PB2(SS/OC1B)_16") (pintype "bidirectional"))
    )
    (net (code "58") (name "unconnected-(U1-PB3(MOSI{slash}OC2)-Pad17)") (class "Default")
      (node (ref "U1") (pin "17") (pinfunction "PB3(MOSI/OC2)_17") (pintype "bidirectional"))
    )
    (net (code "59") (name "unconnected-(U1-PB4(MISO)-Pad18)") (class "Default")
      (node (ref "U1") (pin "18") (pinfunction "PB4(MISO)_18") (pintype "bidirectional"))
    )
    (net (code "60") (name "unconnected-(U1-PB5(SCK)-Pad19)") (class "Default")
      (node (ref "U1") (pin "19") (pinfunction "PB5(SCK)_19") (pintype "bidirectional"))
    )
    (net (code "61") (name "unconnected-(U1-PB7(XTAL2{slash}TOSC2)-Pad10)") (class "Default")
      (node (ref "U1") (pin "10") (pinfunction "PB7(XTAL2/TOSC2)_10") (pintype "bidirectional"))
    )
    (net (code "62") (name "unconnected-(U2-IOA1-Pad41)") (class "Default")
      (node (ref "U2") (pin "41") (pinfunction "IOA1_41") (pintype "bidirectional"))
    )
    (net (code "63") (name "unconnected-(U2-IOA5-Pad2)") (class "Default")
      (node (ref "U2") (pin "2") (pinfunction "IOA5_2") (pintype "bidirectional"))
    )
    (net (code "64") (name "unconnected-(U2-IOA13-Pad14)") (class "Default")
      (node (ref "U2") (pin "14") (pinfunction "IOA13_14") (pintype "bidirectional"))
    )
    (net (code "65") (name "unconnected-(U2-IOA14-Pad15)") (class "Default")
      (node (ref "U2") (pin "15") (pinfunction "IOA14_15") (pintype "bidirectional"))
    )
    (net (code "66") (name "unconnected-(U2-IOB0-Pad18)") (class "Default")
      (node (ref "U2") (pin "18") (pinfunction "IOB0_18") (pintype "bidirectional"))
    )
    (net (code "67") (name "unconnected-(U2-IOB1-Pad19)") (class "Default")
      (node (ref "U2") (pin "19") (pinfunction "IOB1_19") (pintype "bidirectional"))
    )
    (net (code "68") (name "unconnected-(U2-IOB2-Pad20)") (class "Default")
      (node (ref "U2") (pin "20") (pinfunction "IOB2_20") (pintype "bidirectional"))
    )
    (net (code "69") (name "unconnected-(U2-IOB3-Pad21)") (class "Default")
      (node (ref "U2") (pin "21") (pinfunction "IOB3_21") (pintype "bidirectional"))
    )
    (net (code "70") (name "unconnected-(U2-IOB4-Pad22)") (class "Default")
      (node (ref "U2") (pin "22") (pinfunction "IOB4_22") (pintype "bidirectional"))
    )
    (net (code "71") (name "unconnected-(U2-IOB5-Pad24)") (class "Default")
      (node (ref "U2") (pin "24") (pinfunction "IOB5_24") (pintype "bidirectional"))
    )
    (net (code "72") (name "unconnected-(U2-IOB6-Pad25)") (class "Default")
      (node (ref "U2") (pin "25") (pinfunction "IOB6_25") (pintype "bidirectional"))
    )
    (net (code "73") (name "unconnected-(U2-IOB7-Pad26)") (class "Default")
      (node (ref "U2") (pin "26") (pinfunction "IOB7_26") (pintype "bidirectional"))
    )
    (net (code "74") (name "unconnected-(U2-IOB8-Pad29)") (class "Default")
      (node (ref "U2") (pin "29") (pinfunction "IOB8_29") (pintype "bidirectional"))
    )
    (net (code "75") (name "unconnected-(U2-IOB9-Pad30)") (class "Default")
      (node (ref "U2") (pin "30") (pinfunction "IOB9_30") (pintype "bidirectional"))
    )
    (net (code "76") (name "unconnected-(U3A-~{Q}-Pad4)") (class "Default")
      (node (ref "U3") (pin "4") (pinfunction "~{Q}_4") (pintype "output"))
    )
    (net (code "77") (name "unconnected-(U3B-~{Q}-Pad12)") (class "Default")
      (node (ref "U3") (pin "12") (pinfunction "~{Q}_12") (pintype "output"))
    )
    (net (code "78") (name "unconnected-(U8-BOOTSEL-Pad18)") (class "Default")
      (node (ref "U8") (pin "18") (pinfunction "BOOTSEL_18") (pintype "input"))
    )
    (net (code "79") (name "unconnected-(U8-RESERVED-Pad1)") (class "Default")
      (node (ref "U8") (pin "1") (pinfunction "RESERVED_1") (pintype "no_connect"))
    )
    (net (code "80") (name "unconnected-(U8-RESERVED-Pad2)") (class "Default")
      (node (ref "U8") (pin "2") (pinfunction "RESERVED_2") (pintype "no_connect"))
    )
    (net (code "81") (name "unconnected-(U8-RESERVED-Pad7)") (class "Default")
      (node (ref "U8") (pin "7") (pinfunction "RESERVED_7") (pintype "no_connect"))
    )
    (net (code "82") (name "unconnected-(U8-RESERVED-Pad8)") (class "Default")
      (node (ref "U8") (pin "8") (pinfunction "RESERVED_8") (pintype "no_connect"))
    )
    (net (code "83") (name "unconnected-(U8-RESERVED-Pad9)") (class "Default")
      (node (ref "U8") (pin "9") (pinfunction "RESERVED_9") (pintype "no_connect"))
    )
    (net (code "84") (name "unconnected-(U8-RESERVED-Pad10)") (class "Default")
      (node (ref "U8") (pin "10") (pinfunction "RESERVED_10") (pintype "no_connect"))
    )
    (net (code "85") (name "unconnected-(U8-RESERVED-Pad14)") (class "Default")
      (node (ref "U8") (pin "14") (pinfunction "RESERVED_14") (pintype "no_connect"))
    )
    (net (code "86") (name "unconnected-(U8-RESERVED-Pad15)") (class "Default")
      (node (ref "U8") (pin "15") (pinfunction "RESERVED_15") (pintype "no_connect"))
    )
    (net (code "87") (name "unconnected-(U8-RESERVED-Pad16)") (class "Default")
      (node (ref "U8") (pin "16") (pinfunction "RESERVED_16") (pintype "no_connect"))
    )
  )
)
